# ArduinoInterface_v3.net
KiCad netlist of a schematic drawn in EAGLE
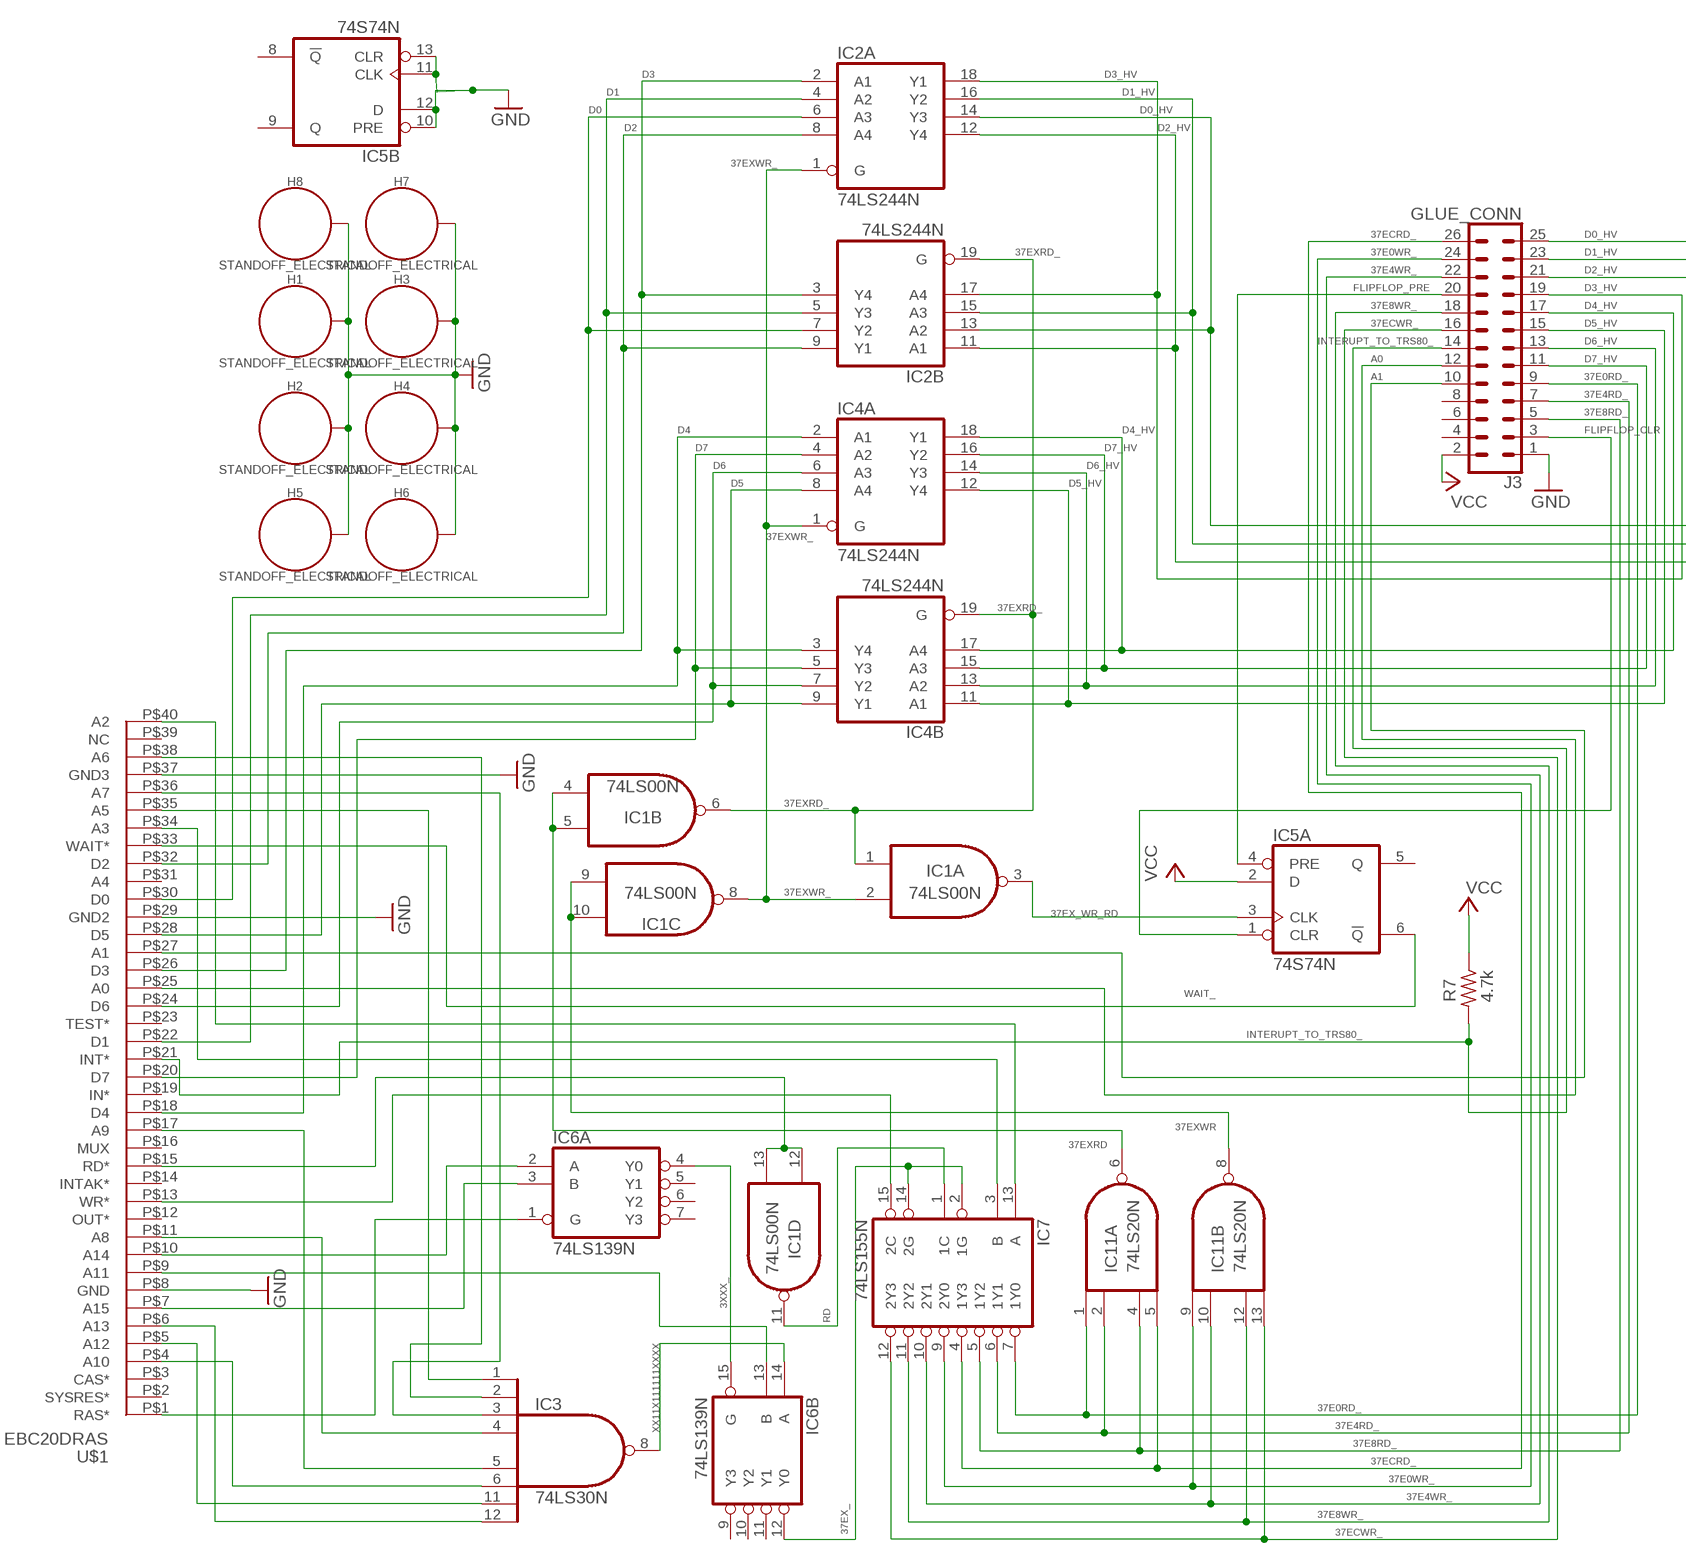
[diagram p0: schematic, sheet 1, part 1 of 2]
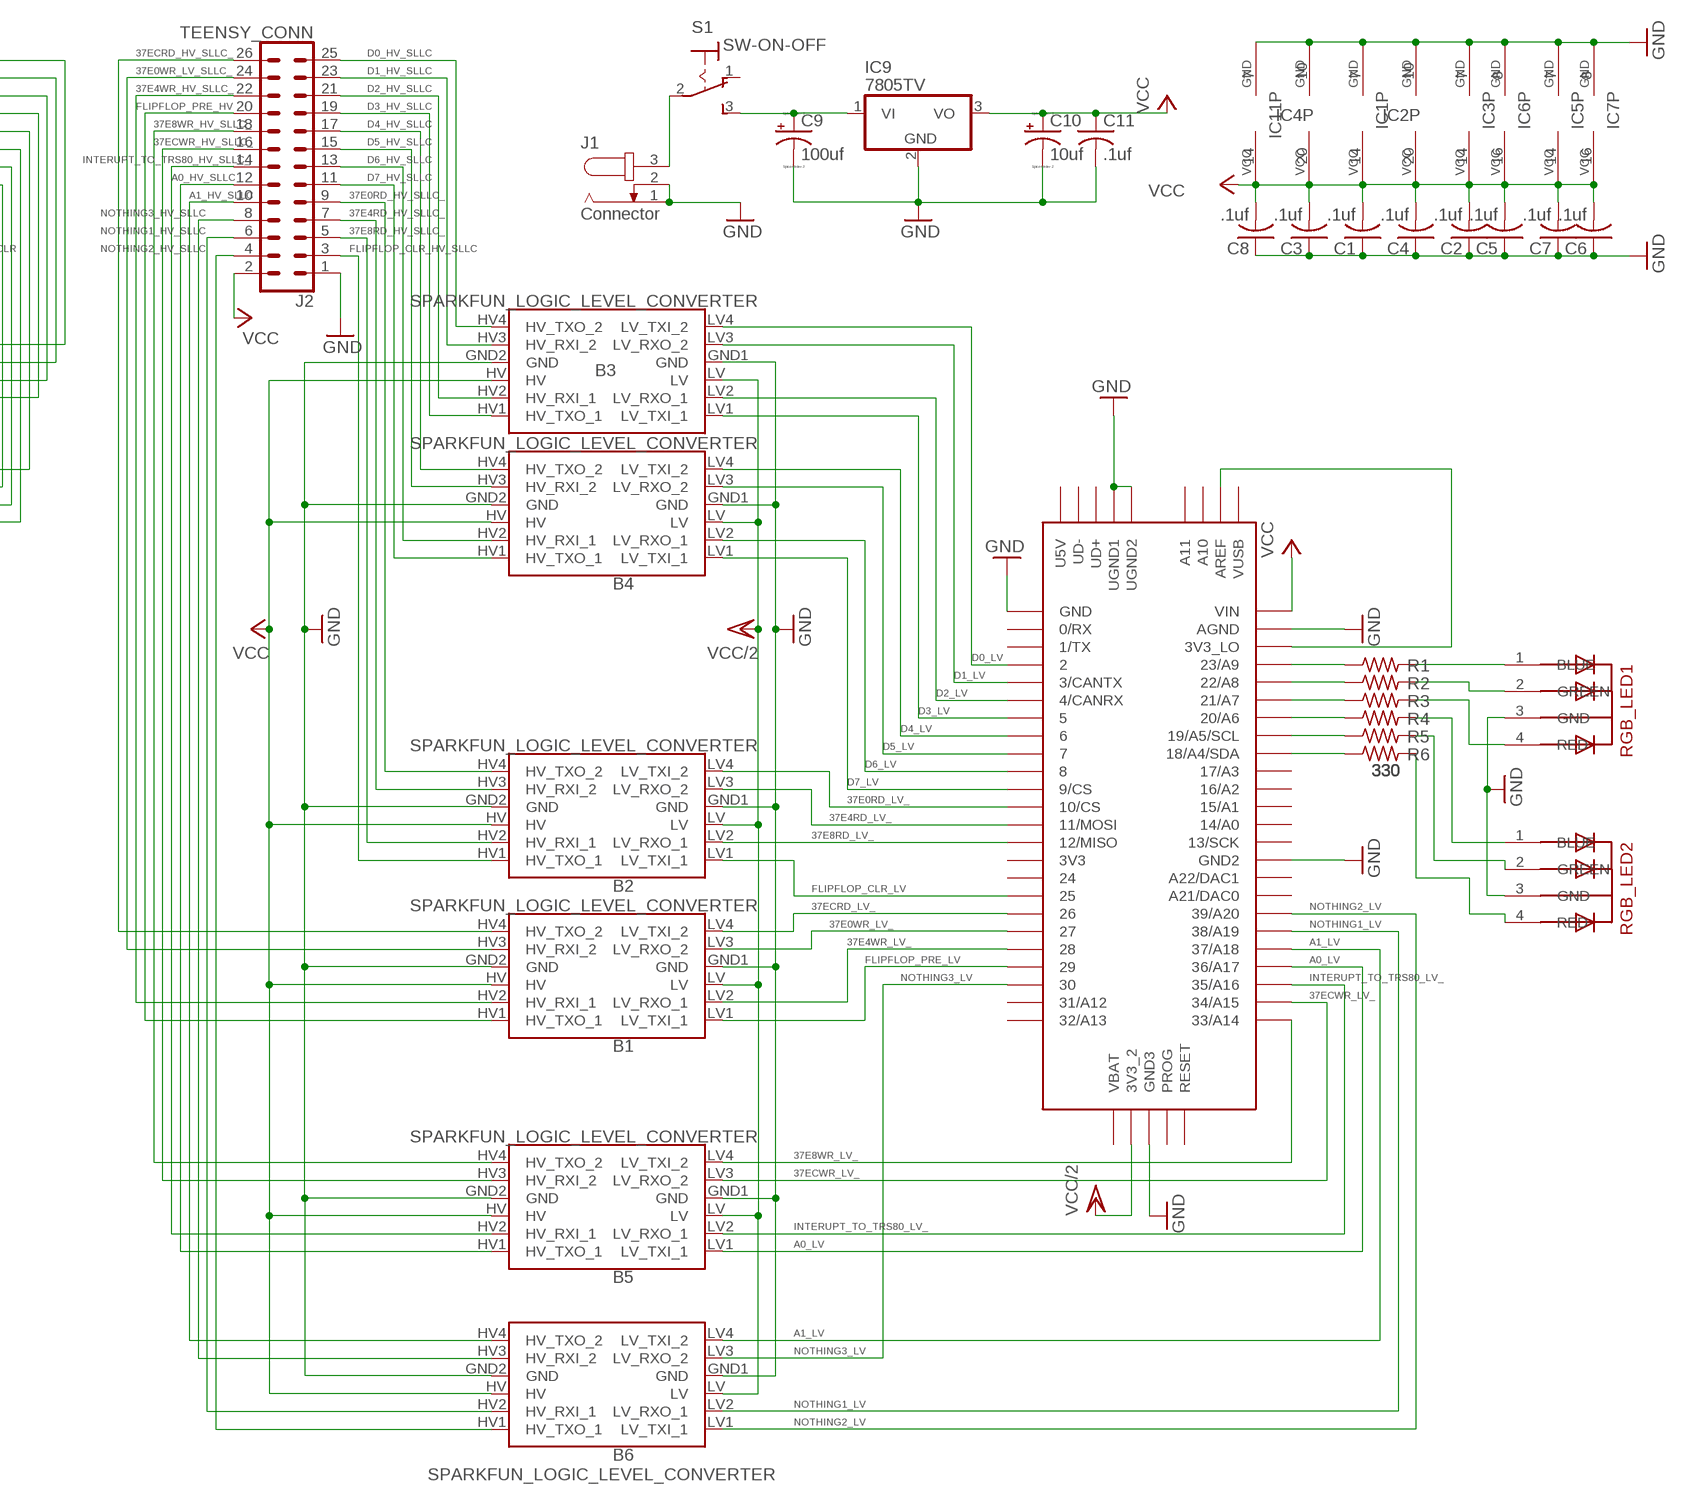
[diagram p1: schematic, sheet 1, part 2 of 2]

(export (version "E")
  (design (tool "Eeschema 10.0.6"))
  (components
    (comp (ref "B1")
      (value "SPARKFUN_LOGIC_LEVEL_CONVERTER")
      (footprint "eagle-import:SPARKFUN_LOGIC_LEVEL_CONVERTER")
      (libsource (lib "eagle-import") (part "SPARKFUN_LOGIC_LEVEL_CONVERTER"))
    )
    (comp (ref "B2")
      (value "SPARKFUN_LOGIC_LEVEL_CONVERTER")
      (footprint "eagle-import:SPARKFUN_LOGIC_LEVEL_CONVERTER")
      (libsource (lib "eagle-import") (part "SPARKFUN_LOGIC_LEVEL_CONVERTER"))
    )
    (comp (ref "B3")
      (value "SPARKFUN_LOGIC_LEVEL_CONVERTER")
      (footprint "eagle-import:SPARKFUN_LOGIC_LEVEL_CONVERTER")
      (libsource (lib "eagle-import") (part "SPARKFUN_LOGIC_LEVEL_CONVERTER"))
    )
    (comp (ref "B4")
      (value "SPARKFUN_LOGIC_LEVEL_CONVERTER")
      (footprint "eagle-import:SPARKFUN_LOGIC_LEVEL_CONVERTER")
      (libsource (lib "eagle-import") (part "SPARKFUN_LOGIC_LEVEL_CONVERTER"))
    )
    (comp (ref "B5")
      (value "SPARKFUN_LOGIC_LEVEL_CONVERTER")
      (footprint "eagle-import:SPARKFUN_LOGIC_LEVEL_CONVERTER")
      (libsource (lib "eagle-import") (part "SPARKFUN_LOGIC_LEVEL_CONVERTER"))
    )
    (comp (ref "B6")
      (value "SPARKFUN_LOGIC_LEVEL_CONVERTER")
      (footprint "eagle-import:SPARKFUN_LOGIC_LEVEL_CONVERTER")
      (libsource (lib "eagle-import") (part "SPARKFUN_LOGIC_LEVEL_CONVERTER"))
    )
    (comp (ref "C1")
      (value ".1uf")
      (footprint "eagle-import:C025-025X050")
      (libsource (lib "eagle-import") (part "C-US025-025X050"))
    )
    (comp (ref "C2")
      (value ".1uf")
      (footprint "eagle-import:C025-025X050")
      (libsource (lib "eagle-import") (part "C-US025-025X050"))
    )
    (comp (ref "C3")
      (value ".1uf")
      (footprint "eagle-import:C025-025X050")
      (libsource (lib "eagle-import") (part "C-US025-025X050"))
    )
    (comp (ref "C4")
      (value ".1uf")
      (footprint "eagle-import:C025-025X050")
      (libsource (lib "eagle-import") (part "C-US025-025X050"))
    )
    (comp (ref "C5")
      (value ".1uf")
      (footprint "eagle-import:C025-025X050")
      (libsource (lib "eagle-import") (part "C-US025-025X050"))
    )
    (comp (ref "C6")
      (value ".1uf")
      (footprint "eagle-import:C025-025X050")
      (libsource (lib "eagle-import") (part "C-US025-025X050"))
    )
    (comp (ref "C7")
      (value ".1uf")
      (footprint "eagle-import:C025-025X050")
      (libsource (lib "eagle-import") (part "C-US025-025X050"))
    )
    (comp (ref "C8")
      (value ".1uf")
      (footprint "eagle-import:C025-025X050")
      (libsource (lib "eagle-import") (part "C-US025-025X050"))
    )
    (comp (ref "C9")
      (value "100uf")
      (footprint "eagle-import:E5-6")
      (libsource (lib "eagle-import") (part "CPOL-USE5-6"))
    )
    (comp (ref "C10")
      (value "10uf")
      (footprint "eagle-import:E5-6")
      (libsource (lib "eagle-import") (part "CPOL-USE5-6"))
    )
    (comp (ref "C11")
      (value ".1uf")
      (footprint "eagle-import:C025-025X050")
      (libsource (lib "eagle-import") (part "C-US025-025X050"))
    )
    (comp (ref "H1")
      (value "STANDOFF_ELECTRICAL")
      (footprint "eagle-import:STANDOFF-ELECTRICAL")
      (libsource (lib "eagle-import") (part "STANDOFF_ELECTRICAL"))
    )
    (comp (ref "H2")
      (value "STANDOFF_ELECTRICAL")
      (footprint "eagle-import:STANDOFF-ELECTRICAL")
      (libsource (lib "eagle-import") (part "STANDOFF_ELECTRICAL"))
    )
    (comp (ref "H3")
      (value "STANDOFF_ELECTRICAL")
      (footprint "eagle-import:STANDOFF-ELECTRICAL")
      (libsource (lib "eagle-import") (part "STANDOFF_ELECTRICAL"))
    )
    (comp (ref "H4")
      (value "STANDOFF_ELECTRICAL")
      (footprint "eagle-import:STANDOFF-ELECTRICAL")
      (libsource (lib "eagle-import") (part "STANDOFF_ELECTRICAL"))
    )
    (comp (ref "H5")
      (value "STANDOFF_ELECTRICAL")
      (footprint "eagle-import:STANDOFF-ELECTRICAL")
      (libsource (lib "eagle-import") (part "STANDOFF_ELECTRICAL"))
    )
    (comp (ref "H6")
      (value "STANDOFF_ELECTRICAL")
      (footprint "eagle-import:STANDOFF-ELECTRICAL")
      (libsource (lib "eagle-import") (part "STANDOFF_ELECTRICAL"))
    )
    (comp (ref "H7")
      (value "STANDOFF_ELECTRICAL")
      (footprint "eagle-import:STANDOFF-ELECTRICAL")
      (libsource (lib "eagle-import") (part "STANDOFF_ELECTRICAL"))
    )
    (comp (ref "H8")
      (value "STANDOFF_ELECTRICAL")
      (footprint "eagle-import:STANDOFF-ELECTRICAL")
      (libsource (lib "eagle-import") (part "STANDOFF_ELECTRICAL"))
    )
    (comp (ref "IC1")
      (value "74LS00N")
      (footprint "eagle-import:DIL14")
      (libsource (lib "eagle-import") (part "7400NLS"))
    )
    (comp (ref "IC2")
      (value "74LS244N")
      (footprint "eagle-import:DIL20")
      (libsource (lib "eagle-import") (part "74244NLS"))
    )
    (comp (ref "IC3")
      (value "74LS30N")
      (footprint "eagle-import:DIL14")
      (libsource (lib "eagle-import") (part "7430NLS"))
    )
    (comp (ref "IC4")
      (value "74LS244N")
      (footprint "eagle-import:DIL20")
      (libsource (lib "eagle-import") (part "74244NLS"))
    )
    (comp (ref "IC5")
      (value "74S74N")
      (footprint "eagle-import:DIL14")
      (libsource (lib "eagle-import") (part "7474NS"))
    )
    (comp (ref "IC6")
      (value "74LS139N")
      (footprint "eagle-import:DIL16")
      (libsource (lib "eagle-import") (part "74139NLS"))
    )
    (comp (ref "IC7")
      (value "74LS155N")
      (footprint "eagle-import:DIL16")
      (libsource (lib "eagle-import") (part "74155NLS"))
    )
    (comp (ref "IC9")
      (value "7805TV")
      (footprint "eagle-import:TO220V")
      (libsource (lib "eagle-import") (part "78TV05"))
    )
    (comp (ref "IC11")
      (value "74LS20N")
      (footprint "eagle-import:DIL14")
      (libsource (lib "eagle-import") (part "7420NLS"))
    )
    (comp (ref "J1")
      (value "Connector")
      (footprint "eagle-import:SPC4077")
      (libsource (lib "eagle-import") (part "JACK-PLUG0"))
    )
    (comp (ref "J2")
      (value "TEENSY_CONN")
      (footprint "eagle-import:2X13")
      (libsource (lib "eagle-import") (part "CONN_13X22X13"))
    )
    (comp (ref "J3")
      (value "GLUE_CONN")
      (footprint "eagle-import:2X13")
      (libsource (lib "eagle-import") (part "CONN_13X22X13"))
    )
    (comp (ref "R1")
      (value "330")
      (footprint "eagle-import:0204V")
      (libsource (lib "eagle-import") (part "R-US_0204/2V"))
    )
    (comp (ref "R2")
      (value "330")
      (footprint "eagle-import:0204V")
      (libsource (lib "eagle-import") (part "R-US_0204/2V"))
    )
    (comp (ref "R3")
      (value "330")
      (footprint "eagle-import:0204V")
      (libsource (lib "eagle-import") (part "R-US_0204/2V"))
    )
    (comp (ref "R4")
      (value "330")
      (footprint "eagle-import:0204V")
      (libsource (lib "eagle-import") (part "R-US_0204/2V"))
    )
    (comp (ref "R5")
      (value "330")
      (footprint "eagle-import:0204V")
      (libsource (lib "eagle-import") (part "R-US_0204/2V"))
    )
    (comp (ref "R6")
      (value "330")
      (footprint "eagle-import:0204V")
      (libsource (lib "eagle-import") (part "R-US_0204/2V"))
    )
    (comp (ref "R7")
      (value "4.7k")
      (footprint "eagle-import:0204V")
      (libsource (lib "eagle-import") (part "R-US_0204/2V"))
    )
    (comp (ref "RGB_LED1")
      (value "5MMRGBLED")
      (footprint "eagle-import:LED5MMRGB")
      (libsource (lib "eagle-import") (part "5MMRGBLED"))
    )
    (comp (ref "RGB_LED2")
      (value "5MMRGBLED")
      (footprint "eagle-import:LED5MMRGB")
      (libsource (lib "eagle-import") (part "5MMRGBLED"))
    )
    (comp (ref "S1")
      (value "SW-ON-OFF")
      (footprint "eagle-import:M9040P")
      (libsource (lib "eagle-import") (part "M9040P"))
    )
    (comp (ref "U$1")
      (value "EBC20DRAS")
      (footprint "eagle-import:EBC20DRAS")
      (libsource (lib "eagle-import") (part "EBC20DRAS"))
    )
    (comp (ref "U$2")
      (value "TEENSY_3.5/3.6")
      (footprint "eagle-import:TEENSY_3.5_3.6")
      (libsource (lib "eagle-import") (part "TEENSY_3.5/3.6"))
    )
  )
  (nets
    (net (code "1") (name "/3XXX_") (class "Default")
      (node (ref "IC6") (pin "15") (pinfunction "G_15") (pintype "input"))
      (node (ref "IC6") (pin "4") (pinfunction "Y0_4") (pintype "output"))
    )
    (net (code "2") (name "/37E0RD_") (class "Default")
      (node (ref "IC11") (pin "1") (pinfunction "I0_1") (pintype "input"))
      (node (ref "IC7") (pin "7") (pinfunction "1Y0_7") (pintype "output"))
      (node (ref "J3") (pin "9") (pinfunction "9_9") (pintype "passive"))
    )
    (net (code "3") (name "/37E0RD_HV_SLLC_") (class "Default")
      (node (ref "B2") (pin "HV4") (pinfunction "HV_TXO_2_HV4") (pintype "bidirectional"))
      (node (ref "J2") (pin "9") (pinfunction "9_9") (pintype "passive"))
    )
    (net (code "4") (name "/37E0RD_LV_") (class "Default")
      (node (ref "B2") (pin "LV4") (pinfunction "LV_TXI_2_LV4") (pintype "bidirectional"))
      (node (ref "U$2") (pin "10/CS") (pinfunction "10/CS_10/CS") (pintype "bidirectional"))
    )
    (net (code "5") (name "/37E0WR_") (class "Default")
      (node (ref "IC11") (pin "9") (pinfunction "I0_9") (pintype "input"))
      (node (ref "IC7") (pin "9") (pinfunction "2Y0_9") (pintype "output"))
      (node (ref "J3") (pin "24") (pinfunction "24_24") (pintype "passive"))
    )
    (net (code "6") (name "/37E0WR_LV_") (class "Default")
      (node (ref "B1") (pin "LV3") (pinfunction "LV_RXO_2_LV3") (pintype "bidirectional"))
      (node (ref "U$2") (pin "27") (pinfunction "27_27") (pintype "bidirectional"))
    )
    (net (code "7") (name "/37E0WR_LV_SLLC_") (class "Default")
      (node (ref "B1") (pin "HV3") (pinfunction "HV_RXI_2_HV3") (pintype "bidirectional"))
      (node (ref "J2") (pin "24") (pinfunction "24_24") (pintype "passive"))
    )
    (net (code "8") (name "/37E4RD_") (class "Default")
      (node (ref "IC11") (pin "2") (pinfunction "I1_2") (pintype "input"))
      (node (ref "IC7") (pin "6") (pinfunction "1Y1_6") (pintype "output"))
      (node (ref "J3") (pin "7") (pinfunction "7_7") (pintype "passive"))
    )
    (net (code "9") (name "/37E4RD_HV_SLLC_") (class "Default")
      (node (ref "B2") (pin "HV3") (pinfunction "HV_RXI_2_HV3") (pintype "bidirectional"))
      (node (ref "J2") (pin "7") (pinfunction "7_7") (pintype "passive"))
    )
    (net (code "10") (name "/37E4RD_LV_") (class "Default")
      (node (ref "B2") (pin "LV3") (pinfunction "LV_RXO_2_LV3") (pintype "bidirectional"))
      (node (ref "U$2") (pin "11/MOSI") (pinfunction "11/MOSI_11/MOSI") (pintype "bidirectional"))
    )
    (net (code "11") (name "/37E4WR_") (class "Default")
      (node (ref "IC11") (pin "10") (pinfunction "I1_10") (pintype "input"))
      (node (ref "IC7") (pin "10") (pinfunction "2Y1_10") (pintype "output"))
      (node (ref "J3") (pin "22") (pinfunction "22_22") (pintype "passive"))
    )
    (net (code "12") (name "/37E4WR_HV_SLLC_") (class "Default")
      (node (ref "B1") (pin "HV2") (pinfunction "HV_RXI_1_HV2") (pintype "bidirectional"))
      (node (ref "J2") (pin "22") (pinfunction "22_22") (pintype "passive"))
    )
    (net (code "13") (name "/37E4WR_LV_") (class "Default")
      (node (ref "B1") (pin "LV2") (pinfunction "LV_RXO_1_LV2") (pintype "bidirectional"))
      (node (ref "U$2") (pin "28") (pinfunction "28_28") (pintype "bidirectional"))
    )
    (net (code "14") (name "/37E8RD_") (class "Default")
      (node (ref "IC11") (pin "4") (pinfunction "I2_4") (pintype "input"))
      (node (ref "IC7") (pin "5") (pinfunction "1Y2_5") (pintype "output"))
      (node (ref "J3") (pin "5") (pinfunction "5_5") (pintype "passive"))
    )
    (net (code "15") (name "/37E8RD_HV_SLLC_") (class "Default")
      (node (ref "B2") (pin "HV2") (pinfunction "HV_RXI_1_HV2") (pintype "bidirectional"))
      (node (ref "J2") (pin "5") (pinfunction "5_5") (pintype "passive"))
    )
    (net (code "16") (name "/37E8RD_LV_") (class "Default")
      (node (ref "B2") (pin "LV2") (pinfunction "LV_RXO_1_LV2") (pintype "bidirectional"))
      (node (ref "U$2") (pin "12/MISO") (pinfunction "12/MISO_12/MISO") (pintype "bidirectional"))
    )
    (net (code "17") (name "/37E8WR_") (class "Default")
      (node (ref "IC11") (pin "12") (pinfunction "I2_12") (pintype "input"))
      (node (ref "IC7") (pin "11") (pinfunction "2Y2_11") (pintype "output"))
      (node (ref "J3") (pin "18") (pinfunction "18_18") (pintype "passive"))
    )
    (net (code "18") (name "/37E8WR_HV_SLLC_") (class "Default")
      (node (ref "B5") (pin "HV4") (pinfunction "HV_TXO_2_HV4") (pintype "bidirectional"))
      (node (ref "J2") (pin "18") (pinfunction "18_18") (pintype "passive"))
    )
    (net (code "19") (name "/37E8WR_LV_") (class "Default")
      (node (ref "B5") (pin "LV4") (pinfunction "LV_TXI_2_LV4") (pintype "bidirectional"))
      (node (ref "U$2") (pin "33/A14") (pinfunction "33/A14_33/A14") (pintype "bidirectional"))
    )
    (net (code "20") (name "/37ECRD_") (class "Default")
      (node (ref "IC11") (pin "5") (pinfunction "I3_5") (pintype "input"))
      (node (ref "IC7") (pin "4") (pinfunction "1Y3_4") (pintype "output"))
      (node (ref "J3") (pin "26") (pinfunction "26_26") (pintype "passive"))
    )
    (net (code "21") (name "/37ECRD_HV_SLLC_") (class "Default")
      (node (ref "B1") (pin "HV4") (pinfunction "HV_TXO_2_HV4") (pintype "bidirectional"))
      (node (ref "J2") (pin "26") (pinfunction "26_26") (pintype "passive"))
    )
    (net (code "22") (name "/37ECRD_LV_") (class "Default")
      (node (ref "B1") (pin "LV4") (pinfunction "LV_TXI_2_LV4") (pintype "bidirectional"))
      (node (ref "U$2") (pin "26") (pinfunction "26_26") (pintype "bidirectional"))
    )
    (net (code "23") (name "/37ECWR_") (class "Default")
      (node (ref "IC11") (pin "13") (pinfunction "I3_13") (pintype "input"))
      (node (ref "IC7") (pin "12") (pinfunction "2Y3_12") (pintype "output"))
      (node (ref "J3") (pin "16") (pinfunction "16_16") (pintype "passive"))
    )
    (net (code "24") (name "/37ECWR_HV_SLLC_") (class "Default")
      (node (ref "B5") (pin "HV3") (pinfunction "HV_RXI_2_HV3") (pintype "bidirectional"))
      (node (ref "J2") (pin "16") (pinfunction "16_16") (pintype "passive"))
    )
    (net (code "25") (name "/37ECWR_LV_") (class "Default")
      (node (ref "B5") (pin "LV3") (pinfunction "LV_RXO_2_LV3") (pintype "bidirectional"))
      (node (ref "U$2") (pin "34/A15") (pinfunction "34/A15_34/A15") (pintype "bidirectional"))
    )
    (net (code "26") (name "/37EXRD") (class "Default")
      (node (ref "IC1") (pin "4") (pinfunction "I0_4") (pintype "input"))
      (node (ref "IC1") (pin "5") (pinfunction "I1_5") (pintype "input"))
      (node (ref "IC11") (pin "6") (pinfunction "O_6") (pintype "output"))
    )
    (net (code "27") (name "/37EXRD_") (class "Default")
      (node (ref "IC1") (pin "1") (pinfunction "I0_1") (pintype "input"))
      (node (ref "IC1") (pin "6") (pinfunction "O_6") (pintype "output"))
      (node (ref "IC2") (pin "19") (pinfunction "G_19") (pintype "input"))
      (node (ref "IC4") (pin "19") (pinfunction "G_19") (pintype "input"))
    )
    (net (code "28") (name "/37EXWR") (class "Default")
      (node (ref "IC1") (pin "10") (pinfunction "I1_10") (pintype "input"))
      (node (ref "IC1") (pin "9") (pinfunction "I0_9") (pintype "input"))
      (node (ref "IC11") (pin "8") (pinfunction "O_8") (pintype "output"))
    )
    (net (code "29") (name "/37EXWR_") (class "Default")
      (node (ref "IC1") (pin "2") (pinfunction "I1_2") (pintype "input"))
      (node (ref "IC1") (pin "8") (pinfunction "O_8") (pintype "output"))
      (node (ref "IC2") (pin "1") (pinfunction "G_1") (pintype "input"))
      (node (ref "IC4") (pin "1") (pinfunction "G_1") (pintype "input"))
    )
    (net (code "30") (name "/37EX_") (class "Default")
      (node (ref "IC6") (pin "12") (pinfunction "Y0_12") (pintype "output"))
      (node (ref "IC7") (pin "14") (pinfunction "2G_14") (pintype "input"))
      (node (ref "IC7") (pin "2") (pinfunction "1G_2") (pintype "input"))
    )
    (net (code "31") (name "/37EX_WR_RD") (class "Default")
      (node (ref "IC1") (pin "3") (pinfunction "O_3") (pintype "output"))
      (node (ref "IC5") (pin "3") (pinfunction "CLK_3") (pintype "input"))
    )
    (net (code "32") (name "/A0") (class "Default")
      (node (ref "J3") (pin "12") (pinfunction "12_12") (pintype "passive"))
      (node (ref "U$1") (pin "P$25") (pinfunction "A0_P$25") (pintype "bidirectional"))
    )
    (net (code "33") (name "/A0_HV_SLLC") (class "Default")
      (node (ref "B5") (pin "HV1") (pinfunction "HV_TXO_1_HV1") (pintype "bidirectional"))
      (node (ref "J2") (pin "12") (pinfunction "12_12") (pintype "passive"))
    )
    (net (code "34") (name "/A0_LV") (class "Default")
      (node (ref "B5") (pin "LV1") (pinfunction "LV_TXI_1_LV1") (pintype "bidirectional"))
      (node (ref "U$2") (pin "36/A17") (pinfunction "36/A17_36/A17") (pintype "bidirectional"))
    )
    (net (code "35") (name "/A1") (class "Default")
      (node (ref "J3") (pin "10") (pinfunction "10_10") (pintype "passive"))
      (node (ref "U$1") (pin "P$27") (pinfunction "A1_P$27") (pintype "bidirectional"))
    )
    (net (code "36") (name "/A1_HV_SLLC") (class "Default")
      (node (ref "B6") (pin "HV4") (pinfunction "HV_TXO_2_HV4") (pintype "bidirectional"))
      (node (ref "J2") (pin "10") (pinfunction "10_10") (pintype "passive"))
    )
    (net (code "37") (name "/A1_LV") (class "Default")
      (node (ref "B6") (pin "LV4") (pinfunction "LV_TXI_2_LV4") (pintype "bidirectional"))
      (node (ref "U$2") (pin "37/A18") (pinfunction "37/A18_37/A18") (pintype "bidirectional"))
    )
    (net (code "38") (name "/D0") (class "Default")
      (node (ref "IC2") (pin "6") (pinfunction "A3_6") (pintype "input"))
      (node (ref "IC2") (pin "7") (pinfunction "Y2_7") (pintype "tri_state"))
      (node (ref "U$1") (pin "P$30") (pinfunction "D0_P$30") (pintype "bidirectional"))
    )
    (net (code "39") (name "/D0_HV") (class "Default")
      (node (ref "IC2") (pin "13") (pinfunction "A2_13") (pintype "input"))
      (node (ref "IC2") (pin "14") (pinfunction "Y3_14") (pintype "tri_state"))
      (node (ref "J3") (pin "25") (pinfunction "25_25") (pintype "passive"))
    )
    (net (code "40") (name "/D0_HV_SLLC") (class "Default")
      (node (ref "B3") (pin "HV4") (pinfunction "HV_TXO_2_HV4") (pintype "bidirectional"))
      (node (ref "J2") (pin "25") (pinfunction "25_25") (pintype "passive"))
    )
    (net (code "41") (name "/D0_LV") (class "Default")
      (node (ref "B3") (pin "LV4") (pinfunction "LV_TXI_2_LV4") (pintype "bidirectional"))
      (node (ref "U$2") (pin "2") (pinfunction "2_2") (pintype "bidirectional"))
    )
    (net (code "42") (name "/D1") (class "Default")
      (node (ref "IC2") (pin "4") (pinfunction "A2_4") (pintype "input"))
      (node (ref "IC2") (pin "5") (pinfunction "Y3_5") (pintype "tri_state"))
      (node (ref "U$1") (pin "P$22") (pinfunction "D1_P$22") (pintype "bidirectional"))
    )
    (net (code "43") (name "/D1_HV") (class "Default")
      (node (ref "IC2") (pin "15") (pinfunction "A3_15") (pintype "input"))
      (node (ref "IC2") (pin "16") (pinfunction "Y2_16") (pintype "tri_state"))
      (node (ref "J3") (pin "23") (pinfunction "23_23") (pintype "passive"))
    )
    (net (code "44") (name "/D1_HV_SLLC") (class "Default")
      (node (ref "B3") (pin "HV3") (pinfunction "HV_RXI_2_HV3") (pintype "bidirectional"))
      (node (ref "J2") (pin "23") (pinfunction "23_23") (pintype "passive"))
    )
    (net (code "45") (name "/D1_LV") (class "Default")
      (node (ref "B3") (pin "LV3") (pinfunction "LV_RXO_2_LV3") (pintype "bidirectional"))
      (node (ref "U$2") (pin "3/CANTX") (pinfunction "3/CANTX_3/CANTX") (pintype "bidirectional"))
    )
    (net (code "46") (name "/D2") (class "Default")
      (node (ref "IC2") (pin "8") (pinfunction "A4_8") (pintype "input"))
      (node (ref "IC2") (pin "9") (pinfunction "Y1_9") (pintype "tri_state"))
      (node (ref "U$1") (pin "P$32") (pinfunction "D2_P$32") (pintype "bidirectional"))
    )
    (net (code "47") (name "/D2_HV") (class "Default")
      (node (ref "IC2") (pin "11") (pinfunction "A1_11") (pintype "input"))
      (node (ref "IC2") (pin "12") (pinfunction "Y4_12") (pintype "tri_state"))
      (node (ref "J3") (pin "21") (pinfunction "21_21") (pintype "passive"))
    )
    (net (code "48") (name "/D2_HV_SLLC") (class "Default")
      (node (ref "B3") (pin "HV2") (pinfunction "HV_RXI_1_HV2") (pintype "bidirectional"))
      (node (ref "J2") (pin "21") (pinfunction "21_21") (pintype "passive"))
    )
    (net (code "49") (name "/D2_LV") (class "Default")
      (node (ref "B3") (pin "LV2") (pinfunction "LV_RXO_1_LV2") (pintype "bidirectional"))
      (node (ref "U$2") (pin "4/CANRX") (pinfunction "4/CANRX_4/CANRX") (pintype "bidirectional"))
    )
    (net (code "50") (name "/D3") (class "Default")
      (node (ref "IC2") (pin "2") (pinfunction "A1_2") (pintype "input"))
      (node (ref "IC2") (pin "3") (pinfunction "Y4_3") (pintype "tri_state"))
      (node (ref "U$1") (pin "P$26") (pinfunction "D3_P$26") (pintype "bidirectional"))
    )
    (net (code "51") (name "/D3_HV") (class "Default")
      (node (ref "IC2") (pin "17") (pinfunction "A4_17") (pintype "input"))
      (node (ref "IC2") (pin "18") (pinfunction "Y1_18") (pintype "tri_state"))
      (node (ref "J3") (pin "19") (pinfunction "19_19") (pintype "passive"))
    )
    (net (code "52") (name "/D3_HV_SLLC") (class "Default")
      (node (ref "B3") (pin "HV1") (pinfunction "HV_TXO_1_HV1") (pintype "bidirectional"))
      (node (ref "J2") (pin "19") (pinfunction "19_19") (pintype "passive"))
    )
    (net (code "53") (name "/D3_LV") (class "Default")
      (node (ref "B3") (pin "LV1") (pinfunction "LV_TXI_1_LV1") (pintype "bidirectional"))
      (node (ref "U$2") (pin "5") (pinfunction "5_5") (pintype "bidirectional"))
    )
    (net (code "54") (name "/D4") (class "Default")
      (node (ref "IC4") (pin "2") (pinfunction "A1_2") (pintype "input"))
      (node (ref "IC4") (pin "3") (pinfunction "Y4_3") (pintype "tri_state"))
      (node (ref "U$1") (pin "P$18") (pinfunction "D4_P$18") (pintype "bidirectional"))
    )
    (net (code "55") (name "/D4_HV") (class "Default")
      (node (ref "IC4") (pin "17") (pinfunction "A4_17") (pintype "input"))
      (node (ref "IC4") (pin "18") (pinfunction "Y1_18") (pintype "tri_state"))
      (node (ref "J3") (pin "17") (pinfunction "17_17") (pintype "passive"))
    )
    (net (code "56") (name "/D4_HV_SLLC") (class "Default")
      (node (ref "B4") (pin "HV4") (pinfunction "HV_TXO_2_HV4") (pintype "bidirectional"))
      (node (ref "J2") (pin "17") (pinfunction "17_17") (pintype "passive"))
    )
    (net (code "57") (name "/D4_LV") (class "Default")
      (node (ref "B4") (pin "LV4") (pinfunction "LV_TXI_2_LV4") (pintype "bidirectional"))
      (node (ref "U$2") (pin "6") (pinfunction "6_6") (pintype "bidirectional"))
    )
    (net (code "58") (name "/D5") (class "Default")
      (node (ref "IC4") (pin "8") (pinfunction "A4_8") (pintype "input"))
      (node (ref "IC4") (pin "9") (pinfunction "Y1_9") (pintype "tri_state"))
      (node (ref "U$1") (pin "P$28") (pinfunction "D5_P$28") (pintype "bidirectional"))
    )
    (net (code "59") (name "/D5_HV") (class "Default")
      (node (ref "IC4") (pin "11") (pinfunction "A1_11") (pintype "input"))
      (node (ref "IC4") (pin "12") (pinfunction "Y4_12") (pintype "tri_state"))
      (node (ref "J3") (pin "15") (pinfunction "15_15") (pintype "passive"))
    )
    (net (code "60") (name "/D5_HV_SLLC") (class "Default")
      (node (ref "B4") (pin "HV3") (pinfunction "HV_RXI_2_HV3") (pintype "bidirectional"))
      (node (ref "J2") (pin "15") (pinfunction "15_15") (pintype "passive"))
    )
    (net (code "61") (name "/D5_LV") (class "Default")
      (node (ref "B4") (pin "LV3") (pinfunction "LV_RXO_2_LV3") (pintype "bidirectional"))
      (node (ref "U$2") (pin "7") (pinfunction "7_7") (pintype "bidirectional"))
    )
    (net (code "62") (name "/D6") (class "Default")
      (node (ref "IC4") (pin "6") (pinfunction "A3_6") (pintype "input"))
      (node (ref "IC4") (pin "7") (pinfunction "Y2_7") (pintype "tri_state"))
      (node (ref "U$1") (pin "P$24") (pinfunction "D6_P$24") (pintype "bidirectional"))
    )
    (net (code "63") (name "/D6_HV") (class "Default")
      (node (ref "IC4") (pin "13") (pinfunction "A2_13") (pintype "input"))
      (node (ref "IC4") (pin "14") (pinfunction "Y3_14") (pintype "tri_state"))
      (node (ref "J3") (pin "13") (pinfunction "13_13") (pintype "passive"))
    )
    (net (code "64") (name "/D6_HV_SLLC") (class "Default")
      (node (ref "B4") (pin "HV2") (pinfunction "HV_RXI_1_HV2") (pintype "bidirectional"))
      (node (ref "J2") (pin "13") (pinfunction "13_13") (pintype "passive"))
    )
    (net (code "65") (name "/D6_LV") (class "Default")
      (node (ref "B4") (pin "LV2") (pinfunction "LV_RXO_1_LV2") (pintype "bidirectional"))
      (node (ref "U$2") (pin "8") (pinfunction "8_8") (pintype "bidirectional"))
    )
    (net (code "66") (name "/D7") (class "Default")
      (node (ref "IC4") (pin "4") (pinfunction "A2_4") (pintype "input"))
      (node (ref "IC4") (pin "5") (pinfunction "Y3_5") (pintype "tri_state"))
      (node (ref "U$1") (pin "P$20") (pinfunction "D7_P$20") (pintype "bidirectional"))
    )
    (net (code "67") (name "/D7_HV") (class "Default")
      (node (ref "IC4") (pin "15") (pinfunction "A3_15") (pintype "input"))
      (node (ref "IC4") (pin "16") (pinfunction "Y2_16") (pintype "tri_state"))
      (node (ref "J3") (pin "11") (pinfunction "11_11") (pintype "passive"))
    )
    (net (code "68") (name "/D7_HV_SLLC") (class "Default")
      (node (ref "B4") (pin "HV1") (pinfunction "HV_TXO_1_HV1") (pintype "bidirectional"))
      (node (ref "J2") (pin "11") (pinfunction "11_11") (pintype "passive"))
    )
    (net (code "69") (name "/D7_LV") (class "Default")
      (node (ref "B4") (pin "LV1") (pinfunction "LV_TXI_1_LV1") (pintype "bidirectional"))
      (node (ref "U$2") (pin "9/CS") (pinfunction "9/CS_9/CS") (pintype "bidirectional"))
    )
    (net (code "70") (name "/FLIPFLOP_CLR") (class "Default")
      (node (ref "IC5") (pin "1") (pinfunction "CLR_1") (pintype "input"))
      (node (ref "J3") (pin "3") (pinfunction "3_3") (pintype "passive"))
    )
    (net (code "71") (name "/FLIPFLOP_CLR_HV_SLLC") (class "Default")
      (node (ref "B2") (pin "HV1") (pinfunction "HV_TXO_1_HV1") (pintype "bidirectional"))
      (node (ref "J2") (pin "3") (pinfunction "3_3") (pintype "passive"))
    )
    (net (code "72") (name "/FLIPFLOP_CLR_LV") (class "Default")
      (node (ref "B2") (pin "LV1") (pinfunction "LV_TXI_1_LV1") (pintype "bidirectional"))
      (node (ref "U$2") (pin "25") (pinfunction "25_25") (pintype "bidirectional"))
    )
    (net (code "73") (name "/FLIPFLOP_PRE") (class "Default")
      (node (ref "IC5") (pin "4") (pinfunction "PRE_4") (pintype "input"))
      (node (ref "J3") (pin "20") (pinfunction "20_20") (pintype "passive"))
    )
    (net (code "74") (name "/FLIPFLOP_PRE_HV") (class "Default")
      (node (ref "B1") (pin "HV1") (pinfunction "HV_TXO_1_HV1") (pintype "bidirectional"))
      (node (ref "J2") (pin "20") (pinfunction "20_20") (pintype "passive"))
    )
    (net (code "75") (name "/FLIPFLOP_PRE_LV") (class "Default")
      (node (ref "B1") (pin "LV1") (pinfunction "LV_TXI_1_LV1") (pintype "bidirectional"))
      (node (ref "U$2") (pin "29") (pinfunction "29_29") (pintype "bidirectional"))
    )
    (net (code "76") (name "/INTERUPT_TO_TRS80_") (class "Default")
      (node (ref "J3") (pin "14") (pinfunction "14_14") (pintype "passive"))
      (node (ref "R7") (pin "2") (pinfunction "2_2") (pintype "passive"))
      (node (ref "U$1") (pin "P$21") (pinfunction "INT*_P$21") (pintype "bidirectional"))
    )
    (net (code "77") (name "/INTERUPT_TO_TRS80_HV_SLLC_") (class "Default")
      (node (ref "B5") (pin "HV2") (pinfunction "HV_RXI_1_HV2") (pintype "bidirectional"))
      (node (ref "J2") (pin "14") (pinfunction "14_14") (pintype "passive"))
    )
    (net (code "78") (name "/INTERUPT_TO_TRS80_LV_") (class "Default")
      (node (ref "B5") (pin "LV2") (pinfunction "LV_RXO_1_LV2") (pintype "bidirectional"))
      (node (ref "U$2") (pin "35/A16") (pinfunction "35/A16_35/A16") (pintype "bidirectional"))
    )
    (net (code "79") (name "/NOTHING1_HV_SLLC") (class "Default")
      (node (ref "B6") (pin "HV2") (pinfunction "HV_RXI_1_HV2") (pintype "bidirectional"))
      (node (ref "J2") (pin "6") (pinfunction "6_6") (pintype "passive"))
    )
    (net (code "80") (name "/NOTHING1_LV") (class "Default")
      (node (ref "B6") (pin "LV2") (pinfunction "LV_RXO_1_LV2") (pintype "bidirectional"))
      (node (ref "U$2") (pin "38/A19") (pinfunction "38/A19_38/A19") (pintype "bidirectional"))
    )
    (net (code "81") (name "/NOTHING2_HV_SLLC") (class "Default")
      (node (ref "B6") (pin "HV1") (pinfunction "HV_TXO_1_HV1") (pintype "bidirectional"))
      (node (ref "J2") (pin "4") (pinfunction "4_4") (pintype "passive"))
    )
    (net (code "82") (name "/NOTHING2_LV") (class "Default")
      (node (ref "B6") (pin "LV1") (pinfunction "LV_TXI_1_LV1") (pintype "bidirectional"))
      (node (ref "U$2") (pin "39/A20") (pinfunction "39/A20_39/A20") (pintype "bidirectional"))
    )
    (net (code "83") (name "/NOTHING3_HV_SLLC") (class "Default")
      (node (ref "B6") (pin "HV3") (pinfunction "HV_RXI_2_HV3") (pintype "bidirectional"))
      (node (ref "J2") (pin "8") (pinfunction "8_8") (pintype "passive"))
    )
    (net (code "84") (name "/NOTHING3_LV") (class "Default")
      (node (ref "B6") (pin "LV3") (pinfunction "LV_RXO_2_LV3") (pintype "bidirectional"))
      (node (ref "U$2") (pin "30") (pinfunction "30_30") (pintype "bidirectional"))
    )
    (net (code "85") (name "/RD") (class "Default")
      (node (ref "IC1") (pin "11") (pinfunction "O_11") (pintype "output"))
      (node (ref "IC7") (pin "1") (pinfunction "1C_1") (pintype "input"))
    )
    (net (code "86") (name "/WAIT_") (class "Default")
      (node (ref "IC5") (pin "6") (pinfunction "~{Q}_6") (pintype "output"))
      (node (ref "U$1") (pin "P$33") (pinfunction "WAIT*_P$33") (pintype "bidirectional"))
    )
    (net (code "87") (name "/XX11X111111XXXX") (class "Default")
      (node (ref "IC3") (pin "8") (pinfunction "O_8") (pintype "output"))
      (node (ref "IC6") (pin "14") (pinfunction "A_14") (pintype "input"))
    )
    (net (code "88") (name "GND") (class "Default")
      (node (ref "B1") (pin "GND1") (pinfunction "GND_GND1") (pintype "power_in"))
      (node (ref "B1") (pin "GND2") (pinfunction "GND_GND2") (pintype "power_in"))
      (node (ref "B2") (pin "GND1") (pinfunction "GND_GND1") (pintype "power_in"))
      (node (ref "B2") (pin "GND2") (pinfunction "GND_GND2") (pintype "power_in"))
      (node (ref "B3") (pin "GND1") (pinfunction "GND_GND1") (pintype "power_in"))
      (node (ref "B3") (pin "GND2") (pinfunction "GND_GND2") (pintype "power_in"))
      (node (ref "B4") (pin "GND1") (pinfunction "GND_GND1") (pintype "power_in"))
      (node (ref "B4") (pin "GND2") (pinfunction "GND_GND2") (pintype "power_in"))
      (node (ref "B5") (pin "GND1") (pinfunction "GND_GND1") (pintype "power_in"))
      (node (ref "B5") (pin "GND2") (pinfunction "GND_GND2") (pintype "power_in"))
      (node (ref "B6") (pin "GND1") (pinfunction "GND_GND1") (pintype "power_in"))
      (node (ref "B6") (pin "GND2") (pinfunction "GND_GND2") (pintype "power_in"))
      (node (ref "C1") (pin "1") (pinfunction "1_1") (pintype "passive"))
      (node (ref "C10") (pin "-") (pinfunction "-_-") (pintype "passive"))
      (node (ref "C11") (pin "2") (pinfunction "2_2") (pintype "passive"))
      (node (ref "C2") (pin "1") (pinfunction "1_1") (pintype "passive"))
      (node (ref "C3") (pin "1") (pinfunction "1_1") (pintype "passive"))
      (node (ref "C4") (pin "1") (pinfunction "1_1") (pintype "passive"))
      (node (ref "C5") (pin "1") (pinfunction "1_1") (pintype "passive"))
      (node (ref "C6") (pin "1") (pinfunction "1_1") (pintype "passive"))
      (node (ref "C7") (pin "1") (pinfunction "1_1") (pintype "passive"))
      (node (ref "C8") (pin "1") (pinfunction "1_1") (pintype "passive"))
      (node (ref "C9") (pin "-") (pinfunction "-_-") (pintype "passive"))
      (node (ref "H1") (pin "P1") (pinfunction "P$1_P1") (pintype "bidirectional"))
      (node (ref "H2") (pin "P1") (pinfunction "P$1_P1") (pintype "bidirectional"))
      (node (ref "H3") (pin "P1") (pinfunction "P$1_P1") (pintype "bidirectional"))
      (node (ref "H4") (pin "P1") (pinfunction "P$1_P1") (pintype "bidirectional"))
      (node (ref "H5") (pin "P1") (pinfunction "P$1_P1") (pintype "bidirectional"))
      (node (ref "H6") (pin "P1") (pinfunction "P$1_P1") (pintype "bidirectional"))
      (node (ref "H7") (pin "P1") (pinfunction "P$1_P1") (pintype "bidirectional"))
      (node (ref "H8") (pin "P1") (pinfunction "P$1_P1") (pintype "bidirectional"))
      (node (ref "IC1") (pin "7") (pinfunction "GND_7") (pintype "power_in"))
      (node (ref "IC11") (pin "7") (pinfunction "GND_7") (pintype "power_in"))
      (node (ref "IC2") (pin "10") (pinfunction "GND_10") (pintype "power_in"))
      (node (ref "IC3") (pin "7") (pinfunction "GND_7") (pintype "power_in"))
      (node (ref "IC4") (pin "10") (pinfunction "GND_10") (pintype "power_in"))
      (node (ref "IC5") (pin "10") (pinfunction "PRE_10") (pintype "input"))
      (node (ref "IC5") (pin "11") (pinfunction "CLK_11") (pintype "input"))
      (node (ref "IC5") (pin "12") (pinfunction "D_12") (pintype "input"))
      (node (ref "IC5") (pin "13") (pinfunction "CLR_13") (pintype "input"))
      (node (ref "IC5") (pin "7") (pinfunction "GND_7") (pintype "power_in"))
      (node (ref "IC6") (pin "8") (pinfunction "GND_8") (pintype "power_in"))
      (node (ref "IC7") (pin "8") (pinfunction "GND_8") (pintype "power_in"))
      (node (ref "IC9") (pin "2") (pinfunction "GND_2") (pintype "passive"))
      (node (ref "J1") (pin "1") (pinfunction "1_1") (pintype "passive"))
      (node (ref "J1") (pin "2") (pinfunction "2_2") (pintype "passive"))
      (node (ref "J2") (pin "1") (pinfunction "1_1") (pintype "passive"))
      (node (ref "J3") (pin "1") (pinfunction "1_1") (pintype "passive"))
      (node (ref "RGB_LED1") (pin "3") (pinfunction "GND_3") (pintype "bidirectional"))
      (node (ref "RGB_LED2") (pin "3") (pinfunction "GND_3") (pintype "bidirectional"))
      (node (ref "U$1") (pin "P$29") (pinfunction "GND2_P$29") (pintype "bidirectional"))
      (node (ref "U$1") (pin "P$37") (pinfunction "GND3_P$37") (pintype "bidirectional"))
      (node (ref "U$1") (pin "P$8") (pinfunction "GND_P$8") (pintype "bidirectional"))
      (node (ref "U$2") (pin "AGND") (pinfunction "AGND_AGND") (pintype "bidirectional"))
      (node (ref "U$2") (pin "GND") (pinfunction "GND_GND") (pintype "bidirectional"))
      (node (ref "U$2") (pin "GND2") (pinfunction "GND2_GND2") (pintype "bidirectional"))
      (node (ref "U$2") (pin "GND3") (pinfunction "GND3_GND3") (pintype "bidirectional"))
      (node (ref "U$2") (pin "UGND1") (pinfunction "UGND1_UGND1") (pintype "bidirectional"))
      (node (ref "U$2") (pin "UGND2") (pinfunction "UGND2_UGND2") (pintype "bidirectional"))
    )
    (net (code "89") (name "Net-(IC1D-I0)") (class "Default")
      (node (ref "IC1") (pin "12") (pinfunction "I0_12") (pintype "input"))
      (node (ref "IC1") (pin "13") (pinfunction "I1_13") (pintype "input"))
      (node (ref "U$1") (pin "P$15") (pinfunction "RD*_P$15") (pintype "bidirectional"))
    )
    (net (code "90") (name "Net-(IC3A-I0)") (class "Default")
      (node (ref "IC3") (pin "1") (pinfunction "I0_1") (pintype "input"))
      (node (ref "U$1") (pin "P$35") (pinfunction "A5_P$35") (pintype "bidirectional"))
    )
    (net (code "91") (name "Net-(IC3A-I1)") (class "Default")
      (node (ref "IC3") (pin "2") (pinfunction "I1_2") (pintype "input"))
      (node (ref "U$1") (pin "P$38") (pinfunction "A6_P$38") (pintype "bidirectional"))
    )
    (net (code "92") (name "Net-(IC3A-I2)") (class "Default")
      (node (ref "IC3") (pin "3") (pinfunction "I2_3") (pintype "input"))
      (node (ref "U$1") (pin "P$36") (pinfunction "A7_P$36") (pintype "bidirectional"))
    )
    (net (code "93") (name "Net-(IC3A-I3)") (class "Default")
      (node (ref "IC3") (pin "4") (pinfunction "I3_4") (pintype "input"))
      (node (ref "U$1") (pin "P$11") (pinfunction "A8_P$11") (pintype "bidirectional"))
    )
    (net (code "94") (name "Net-(IC3A-I4)") (class "Default")
      (node (ref "IC3") (pin "5") (pinfunction "I4_5") (pintype "input"))
      (node (ref "U$1") (pin "P$17") (pinfunction "A9_P$17") (pintype "bidirectional"))
    )
    (net (code "95") (name "Net-(IC3A-I5)") (class "Default")
      (node (ref "IC3") (pin "6") (pinfunction "I5_6") (pintype "input"))
      (node (ref "U$1") (pin "P$4") (pinfunction "A10_P$4") (pintype "bidirectional"))
    )
    (net (code "96") (name "Net-(IC3A-I6)") (class "Default")
      (node (ref "IC3") (pin "11") (pinfunction "I6_11") (pintype "input"))
      (node (ref "U$1") (pin "P$5") (pinfunction "A12_P$5") (pintype "bidirectional"))
    )
    (net (code "97") (name "Net-(IC3A-I7)") (class "Default")
      (node (ref "IC3") (pin "12") (pinfunction "I7_12") (pintype "input"))
      (node (ref "U$1") (pin "P$6") (pinfunction "A13_P$6") (pintype "bidirectional"))
    )
    (net (code "98") (name "Net-(IC6A-A)") (class "Default")
      (node (ref "IC6") (pin "2") (pinfunction "A_2") (pintype "input"))
      (node (ref "U$1") (pin "P$10") (pinfunction "A14_P$10") (pintype "bidirectional"))
    )
    (net (code "99") (name "Net-(IC6A-B)") (class "Default")
      (node (ref "IC6") (pin "3") (pinfunction "B_3") (pintype "input"))
      (node (ref "U$1") (pin "P$7") (pinfunction "A15_P$7") (pintype "bidirectional"))
    )
    (net (code "100") (name "Net-(IC6A-G)") (class "Default")
      (node (ref "IC6") (pin "1") (pinfunction "G_1") (pintype "input"))
      (node (ref "U$1") (pin "P$1") (pinfunction "RAS*_P$1") (pintype "bidirectional"))
    )
    (net (code "101") (name "Net-(IC6B-B)") (class "Default")
      (node (ref "IC6") (pin "13") (pinfunction "B_13") (pintype "input"))
      (node (ref "U$1") (pin "P$9") (pinfunction "A11_P$9") (pintype "bidirectional"))
    )
    (net (code "102") (name "Net-(IC7A-2C)") (class "Default")
      (node (ref "IC7") (pin "15") (pinfunction "2C_15") (pintype "input"))
      (node (ref "U$1") (pin "P$13") (pinfunction "WR*_P$13") (pintype "bidirectional"))
    )
    (net (code "103") (name "Net-(IC7A-A)") (class "Default")
      (node (ref "IC7") (pin "13") (pinfunction "A_13") (pintype "input"))
      (node (ref "U$1") (pin "P$40") (pinfunction "A2_P$40") (pintype "bidirectional"))
    )
    (net (code "104") (name "Net-(IC7A-B)") (class "Default")
      (node (ref "IC7") (pin "3") (pinfunction "B_3") (pintype "input"))
      (node (ref "U$1") (pin "P$34") (pinfunction "A3_P$34") (pintype "bidirectional"))
    )
    (net (code "105") (name "Net-(IC9-VI)") (class "Default")
      (node (ref "C9") (pin "+") (pinfunction "+_+") (pintype "passive"))
      (node (ref "IC9") (pin "1") (pinfunction "VI_1") (pintype "input"))
      (node (ref "S1") (pin "3") (pinfunction "S_3") (pintype "passive"))
    )
    (net (code "106") (name "Net-(R1-Pad1)") (class "Default")
      (node (ref "R1") (pin "1") (pinfunction "1_1") (pintype "passive"))
      (node (ref "U$2") (pin "23/A9") (pinfunction "23/A9_23/A9") (pintype "bidirectional"))
    )
    (net (code "107") (name "Net-(R2-Pad1)") (class "Default")
      (node (ref "R2") (pin "1") (pinfunction "1_1") (pintype "passive"))
      (node (ref "U$2") (pin "22/A8") (pinfunction "22/A8_22/A8") (pintype "bidirectional"))
    )
    (net (code "108") (name "Net-(R3-Pad1)") (class "Default")
      (node (ref "R3") (pin "1") (pinfunction "1_1") (pintype "passive"))
      (node (ref "U$2") (pin "21/A7") (pinfunction "21/A7_21/A7") (pintype "bidirectional"))
    )
    (net (code "109") (name "Net-(R4-Pad1)") (class "Default")
      (node (ref "R4") (pin "1") (pinfunction "1_1") (pintype "passive"))
      (node (ref "U$2") (pin "20/A6") (pinfunction "20/A6_20/A6") (pintype "bidirectional"))
    )
    (net (code "110") (name "Net-(R5-Pad1)") (class "Default")
      (node (ref "R5") (pin "1") (pinfunction "1_1") (pintype "passive"))
      (node (ref "U$2") (pin "19/A5/SCL") (pinfunction "19/A5/SCL_19/A5/SCL") (pintype "bidirectional"))
    )
    (net (code "111") (name "Net-(R6-Pad1)") (class "Default")
      (node (ref "R6") (pin "1") (pinfunction "1_1") (pintype "passive"))
      (node (ref "U$2") (pin "18/A4/SDA") (pinfunction "18/A4/SDA_18/A4/SDA") (pintype "bidirectional"))
    )
    (net (code "112") (name "Net-(RGB_LED1-BLUE)") (class "Default")
      (node (ref "R1") (pin "2") (pinfunction "2_2") (pintype "passive"))
      (node (ref "RGB_LED1") (pin "1") (pinfunction "BLUE_1") (pintype "bidirectional"))
    )
    (net (code "113") (name "Net-(RGB_LED1-GREEN)") (class "Default")
      (node (ref "R2") (pin "2") (pinfunction "2_2") (pintype "passive"))
      (node (ref "RGB_LED1") (pin "2") (pinfunction "GREEN_2") (pintype "bidirectional"))
    )
    (net (code "114") (name "Net-(RGB_LED1-RED)") (class "Default")
      (node (ref "R3") (pin "2") (pinfunction "2_2") (pintype "passive"))
      (node (ref "RGB_LED1") (pin "4") (pinfunction "RED_4") (pintype "bidirectional"))
    )
    (net (code "115") (name "Net-(RGB_LED2-BLUE)") (class "Default")
      (node (ref "R4") (pin "2") (pinfunction "2_2") (pintype "passive"))
      (node (ref "RGB_LED2") (pin "1") (pinfunction "BLUE_1") (pintype "bidirectional"))
    )
    (net (code "116") (name "Net-(RGB_LED2-GREEN)") (class "Default")
      (node (ref "R5") (pin "2") (pinfunction "2_2") (pintype "passive"))
      (node (ref "RGB_LED2") (pin "2") (pinfunction "GREEN_2") (pintype "bidirectional"))
    )
    (net (code "117") (name "Net-(RGB_LED2-RED)") (class "Default")
      (node (ref "R6") (pin "2") (pinfunction "2_2") (pintype "passive"))
      (node (ref "RGB_LED2") (pin "4") (pinfunction "RED_4") (pintype "bidirectional"))
    )
    (net (code "118") (name "Net-(S1-P)") (class "Default")
      (node (ref "J1") (pin "3") (pinfunction "3_3") (pintype "passive"))
      (node (ref "S1") (pin "2") (pinfunction "P_2") (pintype "passive"))
    )
    (net (code "119") (name "Net-(U$2-Pad3V3_LO)") (class "Default")
      (node (ref "U$2") (pin "3V3_LO") (pinfunction "3V3_LO_3V3_LO") (pintype "bidirectional"))
      (node (ref "U$2") (pin "AREF") (pinfunction "AREF_AREF") (pintype "bidirectional"))
    )
    (net (code "120") (name "VCC") (class "Default")
      (node (ref "B1") (pin "HV") (pinfunction "HV_HV") (pintype "power_in"))
      (node (ref "B2") (pin "HV") (pinfunction "HV_HV") (pintype "power_in"))
      (node (ref "B3") (pin "HV") (pinfunction "HV_HV") (pintype "power_in"))
      (node (ref "B4") (pin "HV") (pinfunction "HV_HV") (pintype "power_in"))
      (node (ref "B5") (pin "HV") (pinfunction "HV_HV") (pintype "power_in"))
      (node (ref "B6") (pin "HV") (pinfunction "HV_HV") (pintype "power_in"))
      (node (ref "C1") (pin "2") (pinfunction "2_2") (pintype "passive"))
      (node (ref "C10") (pin "+") (pinfunction "+_+") (pintype "passive"))
      (node (ref "C11") (pin "1") (pinfunction "1_1") (pintype "passive"))
      (node (ref "C2") (pin "2") (pinfunction "2_2") (pintype "passive"))
      (node (ref "C3") (pin "2") (pinfunction "2_2") (pintype "passive"))
      (node (ref "C4") (pin "2") (pinfunction "2_2") (pintype "passive"))
      (node (ref "C5") (pin "2") (pinfunction "2_2") (pintype "passive"))
      (node (ref "C6") (pin "2") (pinfunction "2_2") (pintype "passive"))
      (node (ref "C7") (pin "2") (pinfunction "2_2") (pintype "passive"))
      (node (ref "C8") (pin "2") (pinfunction "2_2") (pintype "passive"))
      (node (ref "IC1") (pin "14") (pinfunction "VCC_14") (pintype "power_in"))
      (node (ref "IC11") (pin "14") (pinfunction "VCC_14") (pintype "power_in"))
      (node (ref "IC2") (pin "20") (pinfunction "VCC_20") (pintype "power_in"))
      (node (ref "IC3") (pin "14") (pinfunction "VCC_14") (pintype "power_in"))
      (node (ref "IC4") (pin "20") (pinfunction "VCC_20") (pintype "power_in"))
      (node (ref "IC5") (pin "14") (pinfunction "VCC_14") (pintype "power_in"))
      (node (ref "IC5") (pin "2") (pinfunction "D_2") (pintype "input"))
      (node (ref "IC6") (pin "16") (pinfunction "VCC_16") (pintype "power_in"))
      (node (ref "IC7") (pin "16") (pinfunction "VCC_16") (pintype "power_in"))
      (node (ref "IC9") (pin "3") (pinfunction "VO_3") (pintype "passive"))
      (node (ref "J2") (pin "2") (pinfunction "2_2") (pintype "passive"))
      (node (ref "J3") (pin "2") (pinfunction "2_2") (pintype "passive"))
      (node (ref "R7") (pin "1") (pinfunction "1_1") (pintype "passive"))
      (node (ref "U$2") (pin "VIN") (pinfunction "VIN_VIN") (pintype "bidirectional"))
    )
    (net (code "121") (name "VCC{slash}2") (class "Default")
      (node (ref "B1") (pin "LV") (pinfunction "LV_LV") (pintype "power_in"))
      (node (ref "B2") (pin "LV") (pinfunction "LV_LV") (pintype "power_in"))
      (node (ref "B3") (pin "LV") (pinfunction "LV_LV") (pintype "power_in"))
      (node (ref "B4") (pin "LV") (pinfunction "LV_LV") (pintype "power_in"))
      (node (ref "B5") (pin "LV") (pinfunction "LV_LV") (pintype "power_in"))
      (node (ref "B6") (pin "LV") (pinfunction "LV_LV") (pintype "power_in"))
      (node (ref "U$2") (pin "3V3_2") (pinfunction "3V3_2_3V3_2") (pintype "bidirectional"))
    )
    (net (code "122") (name "unconnected-(IC5A-Q-Pad5)") (class "Default")
      (node (ref "IC5") (pin "5") (pinfunction "Q_5") (pintype "output"))
    )
    (net (code "123") (name "unconnected-(IC5B-Q-Pad9)") (class "Default")
      (node (ref "IC5") (pin "9") (pinfunction "Q_9") (pintype "output"))
    )
    (net (code "124") (name "unconnected-(IC5B-~{Q}-Pad8)") (class "Default")
      (node (ref "IC5") (pin "8") (pinfunction "~{Q}_8") (pintype "output"))
    )
    (net (code "125") (name "unconnected-(IC6A-Y1-Pad5)") (class "Default")
      (node (ref "IC6") (pin "5") (pinfunction "Y1_5") (pintype "output"))
    )
    (net (code "126") (name "unconnected-(IC6A-Y2-Pad6)") (class "Default")
      (node (ref "IC6") (pin "6") (pinfunction "Y2_6") (pintype "output"))
    )
    (net (code "127") (name "unconnected-(IC6A-Y3-Pad7)") (class "Default")
      (node (ref "IC6") (pin "7") (pinfunction "Y3_7") (pintype "output"))
    )
    (net (code "128") (name "unconnected-(IC6B-Y1-Pad11)") (class "Default")
      (node (ref "IC6") (pin "11") (pinfunction "Y1_11") (pintype "output"))
    )
    (net (code "129") (name "unconnected-(IC6B-Y2-Pad10)") (class "Default")
      (node (ref "IC6") (pin "10") (pinfunction "Y2_10") (pintype "output"))
    )
    (net (code "130") (name "unconnected-(IC6B-Y3-Pad9)") (class "Default")
      (node (ref "IC6") (pin "9") (pinfunction "Y3_9") (pintype "output"))
    )
    (net (code "131") (name "unconnected-(J3-Pad4)") (class "Default")
      (node (ref "J3") (pin "4") (pinfunction "4_4") (pintype "passive"))
    )
    (net (code "132") (name "unconnected-(J3-Pad6)") (class "Default")
      (node (ref "J3") (pin "6") (pinfunction "6_6") (pintype "passive"))
    )
    (net (code "133") (name "unconnected-(J3-Pad8)") (class "Default")
      (node (ref "J3") (pin "8") (pinfunction "8_8") (pintype "passive"))
    )
    (net (code "134") (name "unconnected-(S1-O-Pad1)") (class "Default")
      (node (ref "S1") (pin "1") (pinfunction "O_1") (pintype "passive"))
    )
    (net (code "135") (name "unconnected-(U$1-A4-PadP$31)") (class "Default")
      (node (ref "U$1") (pin "P$31") (pinfunction "A4_P$31") (pintype "bidirectional"))
    )
    (net (code "136") (name "unconnected-(U$1-CAS*-PadP$3)") (class "Default")
      (node (ref "U$1") (pin "P$3") (pinfunction "CAS*_P$3") (pintype "bidirectional"))
    )
    (net (code "137") (name "unconnected-(U$1-IN*-PadP$19)") (class "Default")
      (node (ref "U$1") (pin "P$19") (pinfunction "IN*_P$19") (pintype "bidirectional"))
    )
    (net (code "138") (name "unconnected-(U$1-INTAK*-PadP$14)") (class "Default")
      (node (ref "U$1") (pin "P$14") (pinfunction "INTAK*_P$14") (pintype "bidirectional"))
    )
    (net (code "139") (name "unconnected-(U$1-MUX-PadP$16)") (class "Default")
      (node (ref "U$1") (pin "P$16") (pinfunction "MUX_P$16") (pintype "bidirectional"))
    )
    (net (code "140") (name "unconnected-(U$1-NC-PadP$39)") (class "Default")
      (node (ref "U$1") (pin "P$39") (pinfunction "NC_P$39") (pintype "bidirectional"))
    )
    (net (code "141") (name "unconnected-(U$1-OUT*-PadP$12)") (class "Default")
      (node (ref "U$1") (pin "P$12") (pinfunction "OUT*_P$12") (pintype "bidirectional"))
    )
    (net (code "142") (name "unconnected-(U$1-SYSRES*-PadP$2)") (class "Default")
      (node (ref "U$1") (pin "P$2") (pinfunction "SYSRES*_P$2") (pintype "bidirectional"))
    )
    (net (code "143") (name "unconnected-(U$1-TEST*-PadP$23)") (class "Default")
      (node (ref "U$1") (pin "P$23") (pinfunction "TEST*_P$23") (pintype "bidirectional"))
    )
    (net (code "144") (name "unconnected-(U$2-A21{slash}DAC0-Pad21{slash}DAC0)") (class "Default")
      (node (ref "U$2") (pin "21/DAC0") (pinfunction "A21/DAC0_21/DAC0") (pintype "bidirectional"))
    )
    (net (code "145") (name "unconnected-(U$2-Pad0{slash}RX)") (class "Default")
      (node (ref "U$2") (pin "0/RX") (pinfunction "0/RX_0/RX") (pintype "bidirectional"))
    )
    (net (code "146") (name "unconnected-(U$2-Pad1{slash}TX)") (class "Default")
      (node (ref "U$2") (pin "1/TX") (pinfunction "1/TX_1/TX") (pintype "bidirectional"))
    )
    (net (code "147") (name "unconnected-(U$2-Pad3V3)") (class "Default")
      (node (ref "U$2") (pin "3V3") (pinfunction "3V3_3V3") (pintype "bidirectional"))
    )
    (net (code "148") (name "unconnected-(U$2-Pad13{slash}SCK)") (class "Default")
      (node (ref "U$2") (pin "13/SCK") (pinfunction "13/SCK_13/SCK") (pintype "bidirectional"))
    )
    (net (code "149") (name "unconnected-(U$2-Pad14{slash}A0)") (class "Default")
      (node (ref "U$2") (pin "14/A0") (pinfunction "14/A0_14/A0") (pintype "bidirectional"))
    )
    (net (code "150") (name "unconnected-(U$2-Pad15{slash}A1)") (class "Default")
      (node (ref "U$2") (pin "15/A1") (pinfunction "15/A1_15/A1") (pintype "bidirectional"))
    )
    (net (code "151") (name "unconnected-(U$2-Pad16{slash}A2)") (class "Default")
      (node (ref "U$2") (pin "16/A2") (pinfunction "16/A2_16/A2") (pintype "bidirectional"))
    )
    (net (code "152") (name "unconnected-(U$2-Pad17{slash}A3)") (class "Default")
      (node (ref "U$2") (pin "17/A3") (pinfunction "17/A3_17/A3") (pintype "bidirectional"))
    )
    (net (code "153") (name "unconnected-(U$2-Pad24)") (class "Default")
      (node (ref "U$2") (pin "24") (pinfunction "24_24") (pintype "bidirectional"))
    )
    (net (code "154") (name "unconnected-(U$2-Pad31{slash}A12)") (class "Default")
      (node (ref "U$2") (pin "31/A12") (pinfunction "31/A12_31/A12") (pintype "bidirectional"))
    )
    (net (code "155") (name "unconnected-(U$2-Pad32{slash}A13)") (class "Default")
      (node (ref "U$2") (pin "32/A13") (pinfunction "32/A13_32/A13") (pintype "bidirectional"))
    )
    (net (code "156") (name "unconnected-(U$2-PadA10)") (class "Default")
      (node (ref "U$2") (pin "A10") (pinfunction "A10_A10") (pintype "bidirectional"))
    )
    (net (code "157") (name "unconnected-(U$2-PadA11)") (class "Default")
      (node (ref "U$2") (pin "A11") (pinfunction "A11_A11") (pintype "bidirectional"))
    )
    (net (code "158") (name "unconnected-(U$2-PadA22{slash}DAC1)") (class "Default")
      (node (ref "U$2") (pin "A22/DAC1") (pinfunction "A22/DAC1_A22/DAC1") (pintype "bidirectional"))
    )
    (net (code "159") (name "unconnected-(U$2-PadPROG)") (class "Default")
      (node (ref "U$2") (pin "PROG") (pinfunction "PROG_PROG") (pintype "bidirectional"))
    )
    (net (code "160") (name "unconnected-(U$2-PadRESET)") (class "Default")
      (node (ref "U$2") (pin "RESET") (pinfunction "RESET_RESET") (pintype "bidirectional"))
    )
    (net (code "161") (name "unconnected-(U$2-PadU5V)") (class "Default")
      (node (ref "U$2") (pin "U5V") (pinfunction "U5V_U5V") (pintype "bidirectional"))
    )
    (net (code "162") (name "unconnected-(U$2-PadUD+)") (class "Default")
      (node (ref "U$2") (pin "UD+") (pinfunction "UD+_UD+") (pintype "bidirectional"))
    )
    (net (code "163") (name "unconnected-(U$2-PadUD-)") (class "Default")
      (node (ref "U$2") (pin "UD-") (pinfunction "UD-_UD-") (pintype "bidirectional"))
    )
    (net (code "164") (name "unconnected-(U$2-PadVBAT)") (class "Default")
      (node (ref "U$2") (pin "VBAT") (pinfunction "VBAT_VBAT") (pintype "bidirectional"))
    )
    (net (code "165") (name "unconnected-(U$2-PadVUSB)") (class "Default")
      (node (ref "U$2") (pin "VUSB") (pinfunction "VUSB_VUSB") (pintype "bidirectional"))
    )
  )
)
